# Processor.net
KiCad netlist of a schematic drawn in Altium Designer
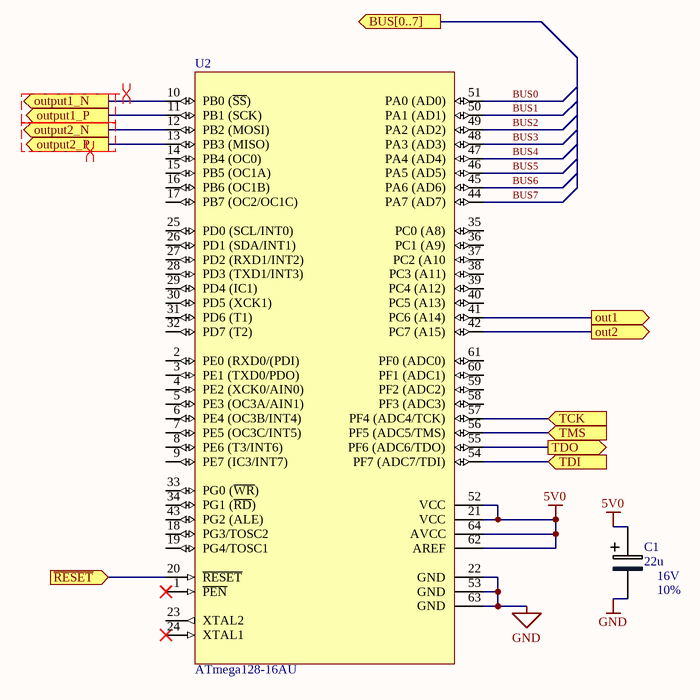
[diagram p0: Processor.SchDoc]

(export (version "E")
  (design (tool "Eeschema 10.0.6"))
  (components
    (comp (ref "C1")
      (value "22u")
      (footprint "VJ_Tantalum_A")
      (fields
        (field (name "MANUFACTURER") "VJ")
        (field (name "PART NUMBER") "293D223X9016D2TE3")
        (field (name "RATED VOLTAGE") "16V")
        (field (name "TOLERANCE") "10%")
      )
      (libsource (lib "Schematic_Library_TK") (part "Capacitor_polarized"))
    )
    (comp (ref "U2")
      (value "ATmega128-16AU")
      (footprint "64A_N")
      (libsource (lib "Schematic_Library_TK") (part "ATmega128-16AU"))
    )
  )
  (nets
    (net (code "1") (name "/BUS0") (class "Default")
      (node (ref "U2") (pin "51") (pinfunction "PA0_(AD0)_51") (pintype "bidirectional"))
    )
    (net (code "2") (name "/BUS1") (class "Default")
      (node (ref "U2") (pin "50") (pinfunction "PA1_(AD1)_50") (pintype "bidirectional"))
    )
    (net (code "3") (name "/BUS2") (class "Default")
      (node (ref "U2") (pin "49") (pinfunction "PA2_(AD2)_49") (pintype "bidirectional"))
    )
    (net (code "4") (name "/BUS3") (class "Default")
      (node (ref "U2") (pin "48") (pinfunction "PA3_(AD3)_48") (pintype "bidirectional"))
    )
    (net (code "5") (name "/BUS4") (class "Default")
      (node (ref "U2") (pin "47") (pinfunction "PA4_(AD4)_47") (pintype "bidirectional"))
    )
    (net (code "6") (name "/BUS5") (class "Default")
      (node (ref "U2") (pin "46") (pinfunction "PA5_(AD5)_46") (pintype "bidirectional"))
    )
    (net (code "7") (name "/BUS6") (class "Default")
      (node (ref "U2") (pin "45") (pinfunction "PA6_(AD6)_45") (pintype "bidirectional"))
    )
    (net (code "8") (name "/BUS7") (class "Default")
      (node (ref "U2") (pin "44") (pinfunction "PA7_(AD7)_44") (pintype "bidirectional"))
    )
    (net (code "10") (name "/TCK") (class "Default")
      (node (ref "U2") (pin "57") (pinfunction "PF4_(ADC4/TCK)_57") (pintype "bidirectional"))
    )
    (net (code "11") (name "/TDI") (class "Default")
      (node (ref "U2") (pin "54") (pinfunction "PF7_(ADC7/TDI)_54") (pintype "bidirectional"))
    )
    (net (code "12") (name "/TDO") (class "Default")
      (node (ref "U2") (pin "55") (pinfunction "PF6_(ADC6/TDO)_55") (pintype "bidirectional"))
    )
    (net (code "13") (name "/TMS") (class "Default")
      (node (ref "U2") (pin "56") (pinfunction "PF5_(ADC5/TMS)_56") (pintype "bidirectional"))
    )
    (net (code "14") (name "/out1") (class "Default")
      (node (ref "U2") (pin "41") (pinfunction "PC6_(A14)_41") (pintype "bidirectional"))
    )
    (net (code "15") (name "/out2") (class "Default")
      (node (ref "U2") (pin "42") (pinfunction "PC7_(A15)_42") (pintype "bidirectional"))
    )
    (net (code "16") (name "/output1_N") (class "Default")
      (node (ref "U2") (pin "10") (pinfunction "PB0_(~{SS})_10") (pintype "bidirectional"))
    )
    (net (code "17") (name "/output1_P") (class "Default")
      (node (ref "U2") (pin "11") (pinfunction "PB1_(SCK)_11") (pintype "bidirectional"))
    )
    (net (code "18") (name "/output2_N") (class "Default")
      (node (ref "U2") (pin "12") (pinfunction "PB2_(MOSI)_12") (pintype "bidirectional"))
    )
    (net (code "19") (name "/output2_P") (class "Default")
      (node (ref "U2") (pin "13") (pinfunction "PB3_(MISO)_13") (pintype "bidirectional"))
    )
    (net (code "20") (name "/~{RESET}") (class "Default")
      (node (ref "U2") (pin "20") (pinfunction "~{RESET}_20") (pintype "input"))
    )
    (net (code "21") (name "5V0") (class "Default")
      (node (ref "C1") (pin "1") (pinfunction "1_1") (pintype "passive"))
      (node (ref "U2") (pin "21") (pinfunction "VCC_21") (pintype "power_in"))
      (node (ref "U2") (pin "52") (pinfunction "VCC_52") (pintype "power_in"))
      (node (ref "U2") (pin "62") (pinfunction "AREF_62") (pintype "passive"))
      (node (ref "U2") (pin "64") (pinfunction "AVCC_64") (pintype "power_in"))
    )
    (net (code "22") (name "GND") (class "Default")
      (node (ref "C1") (pin "2") (pinfunction "2_2") (pintype "passive"))
      (node (ref "U2") (pin "22") (pinfunction "GND_22") (pintype "power_in"))
      (node (ref "U2") (pin "53") (pinfunction "GND_53") (pintype "power_in"))
      (node (ref "U2") (pin "63") (pinfunction "GND_63") (pintype "power_in"))
    )
    (net (code "23") (name "unconnected-(U2-PB4_(OC0)-Pad14)") (class "Default")
      (node (ref "U2") (pin "14") (pinfunction "PB4_(OC0)_14") (pintype "bidirectional"))
    )
    (net (code "24") (name "unconnected-(U2-PB5_(OC1A)-Pad15)") (class "Default")
      (node (ref "U2") (pin "15") (pinfunction "PB5_(OC1A)_15") (pintype "bidirectional"))
    )
    (net (code "25") (name "unconnected-(U2-PB6_(OC1B)-Pad16)") (class "Default")
      (node (ref "U2") (pin "16") (pinfunction "PB6_(OC1B)_16") (pintype "bidirectional"))
    )
    (net (code "26") (name "unconnected-(U2-PB7_(OC2{slash}OC1C)-Pad17)") (class "Default")
      (node (ref "U2") (pin "17") (pinfunction "PB7_(OC2/OC1C)_17") (pintype "bidirectional"))
    )
    (net (code "27") (name "unconnected-(U2-PC0_(A8)-Pad35)") (class "Default")
      (node (ref "U2") (pin "35") (pinfunction "PC0_(A8)_35") (pintype "bidirectional"))
    )
    (net (code "28") (name "unconnected-(U2-PC1_(A9)-Pad36)") (class "Default")
      (node (ref "U2") (pin "36") (pinfunction "PC1_(A9)_36") (pintype "bidirectional"))
    )
    (net (code "29") (name "unconnected-(U2-PC2_(A10-Pad37)") (class "Default")
      (node (ref "U2") (pin "37") (pinfunction "PC2_(A10_37") (pintype "bidirectional"))
    )
    (net (code "30") (name "unconnected-(U2-PC3_(A11)-Pad38)") (class "Default")
      (node (ref "U2") (pin "38") (pinfunction "PC3_(A11)_38") (pintype "bidirectional"))
    )
    (net (code "31") (name "unconnected-(U2-PC4_(A12)-Pad39)") (class "Default")
      (node (ref "U2") (pin "39") (pinfunction "PC4_(A12)_39") (pintype "bidirectional"))
    )
    (net (code "32") (name "unconnected-(U2-PC5_(A13)-Pad40)") (class "Default")
      (node (ref "U2") (pin "40") (pinfunction "PC5_(A13)_40") (pintype "bidirectional"))
    )
    (net (code "33") (name "unconnected-(U2-PD0_(SCL{slash}INT0)-Pad25)") (class "Default")
      (node (ref "U2") (pin "25") (pinfunction "PD0_(SCL/INT0)_25") (pintype "bidirectional"))
    )
    (net (code "34") (name "unconnected-(U2-PD1_(SDA{slash}INT1)-Pad26)") (class "Default")
      (node (ref "U2") (pin "26") (pinfunction "PD1_(SDA/INT1)_26") (pintype "bidirectional"))
    )
    (net (code "35") (name "unconnected-(U2-PD2_(RXD1{slash}INT2)-Pad27)") (class "Default")
      (node (ref "U2") (pin "27") (pinfunction "PD2_(RXD1/INT2)_27") (pintype "bidirectional"))
    )
    (net (code "36") (name "unconnected-(U2-PD3_(TXD1{slash}INT3)-Pad28)") (class "Default")
      (node (ref "U2") (pin "28") (pinfunction "PD3_(TXD1/INT3)_28") (pintype "bidirectional"))
    )
    (net (code "37") (name "unconnected-(U2-PD4_(IC1)-Pad29)") (class "Default")
      (node (ref "U2") (pin "29") (pinfunction "PD4_(IC1)_29") (pintype "bidirectional"))
    )
    (net (code "38") (name "unconnected-(U2-PD5_(XCK1)-Pad30)") (class "Default")
      (node (ref "U2") (pin "30") (pinfunction "PD5_(XCK1)_30") (pintype "bidirectional"))
    )
    (net (code "39") (name "unconnected-(U2-PD6_(T1)-Pad31)") (class "Default")
      (node (ref "U2") (pin "31") (pinfunction "PD6_(T1)_31") (pintype "bidirectional"))
    )
    (net (code "40") (name "unconnected-(U2-PD7_(T2)-Pad32)") (class "Default")
      (node (ref "U2") (pin "32") (pinfunction "PD7_(T2)_32") (pintype "bidirectional"))
    )
    (net (code "41") (name "unconnected-(U2-PE0_(RXD0{slash}(PDI)-Pad2)") (class "Default")
      (node (ref "U2") (pin "2") (pinfunction "PE0_(RXD0/(PDI)_2") (pintype "bidirectional"))
    )
    (net (code "42") (name "unconnected-(U2-PE1_(TXD0{slash}PDO)-Pad3)") (class "Default")
      (node (ref "U2") (pin "3") (pinfunction "PE1_(TXD0/PDO)_3") (pintype "bidirectional"))
    )
    (net (code "43") (name "unconnected-(U2-PE2_(XCK0{slash}AIN0)-Pad4)") (class "Default")
      (node (ref "U2") (pin "4") (pinfunction "PE2_(XCK0/AIN0)_4") (pintype "bidirectional"))
    )
    (net (code "44") (name "unconnected-(U2-PE3_(OC3A{slash}AIN1)-Pad5)") (class "Default")
      (node (ref "U2") (pin "5") (pinfunction "PE3_(OC3A/AIN1)_5") (pintype "bidirectional"))
    )
    (net (code "45") (name "unconnected-(U2-PE4_(OC3B{slash}INT4)-Pad6)") (class "Default")
      (node (ref "U2") (pin "6") (pinfunction "PE4_(OC3B/INT4)_6") (pintype "bidirectional"))
    )
    (net (code "46") (name "unconnected-(U2-PE5_(OC3C{slash}INT5)-Pad7)") (class "Default")
      (node (ref "U2") (pin "7") (pinfunction "PE5_(OC3C/INT5)_7") (pintype "bidirectional"))
    )
    (net (code "47") (name "unconnected-(U2-PE6_(T3{slash}INT6)-Pad8)") (class "Default")
      (node (ref "U2") (pin "8") (pinfunction "PE6_(T3/INT6)_8") (pintype "bidirectional"))
    )
    (net (code "48") (name "unconnected-(U2-PE7_(IC3{slash}INT7)-Pad9)") (class "Default")
      (node (ref "U2") (pin "9") (pinfunction "PE7_(IC3/INT7)_9") (pintype "bidirectional"))
    )
    (net (code "49") (name "unconnected-(U2-PF0_(ADC0)-Pad61)") (class "Default")
      (node (ref "U2") (pin "61") (pinfunction "PF0_(ADC0)_61") (pintype "bidirectional"))
    )
    (net (code "50") (name "unconnected-(U2-PF1_(ADC1)-Pad60)") (class "Default")
      (node (ref "U2") (pin "60") (pinfunction "PF1_(ADC1)_60") (pintype "bidirectional"))
    )
    (net (code "51") (name "unconnected-(U2-PF2_(ADC2)-Pad59)") (class "Default")
      (node (ref "U2") (pin "59") (pinfunction "PF2_(ADC2)_59") (pintype "bidirectional"))
    )
    (net (code "52") (name "unconnected-(U2-PF3_(ADC3)-Pad58)") (class "Default")
      (node (ref "U2") (pin "58") (pinfunction "PF3_(ADC3)_58") (pintype "bidirectional"))
    )
    (net (code "53") (name "unconnected-(U2-PG0_(~{WR})-Pad33)") (class "Default")
      (node (ref "U2") (pin "33") (pinfunction "PG0_(~{WR})_33") (pintype "bidirectional"))
    )
    (net (code "54") (name "unconnected-(U2-PG1_(~{RD})-Pad34)") (class "Default")
      (node (ref "U2") (pin "34") (pinfunction "PG1_(~{RD})_34") (pintype "bidirectional"))
    )
    (net (code "55") (name "unconnected-(U2-PG2_(ALE)-Pad43)") (class "Default")
      (node (ref "U2") (pin "43") (pinfunction "PG2_(ALE)_43") (pintype "bidirectional"))
    )
    (net (code "56") (name "unconnected-(U2-PG3{slash}TOSC2-Pad18)") (class "Default")
      (node (ref "U2") (pin "18") (pinfunction "PG3/TOSC2_18") (pintype "bidirectional"))
    )
    (net (code "57") (name "unconnected-(U2-PG4{slash}TOSC1-Pad19)") (class "Default")
      (node (ref "U2") (pin "19") (pinfunction "PG4/TOSC1_19") (pintype "bidirectional"))
    )
    (net (code "58") (name "unconnected-(U2-XTAL1-Pad24)") (class "Default")
      (node (ref "U2") (pin "24") (pinfunction "XTAL1_24") (pintype "input+no_connect"))
    )
    (net (code "59") (name "unconnected-(U2-XTAL2-Pad23)") (class "Default")
      (node (ref "U2") (pin "23") (pinfunction "XTAL2_23") (pintype "output"))
    )
    (net (code "60") (name "unconnected-(U2-~{PEN}-Pad1)") (class "Default")
      (node (ref "U2") (pin "1") (pinfunction "~{PEN}_1") (pintype "input+no_connect"))
    )
  )
)
